# PiCarHat_Master_V2.net
KiCad netlist of a schematic drawn in Altium Designer
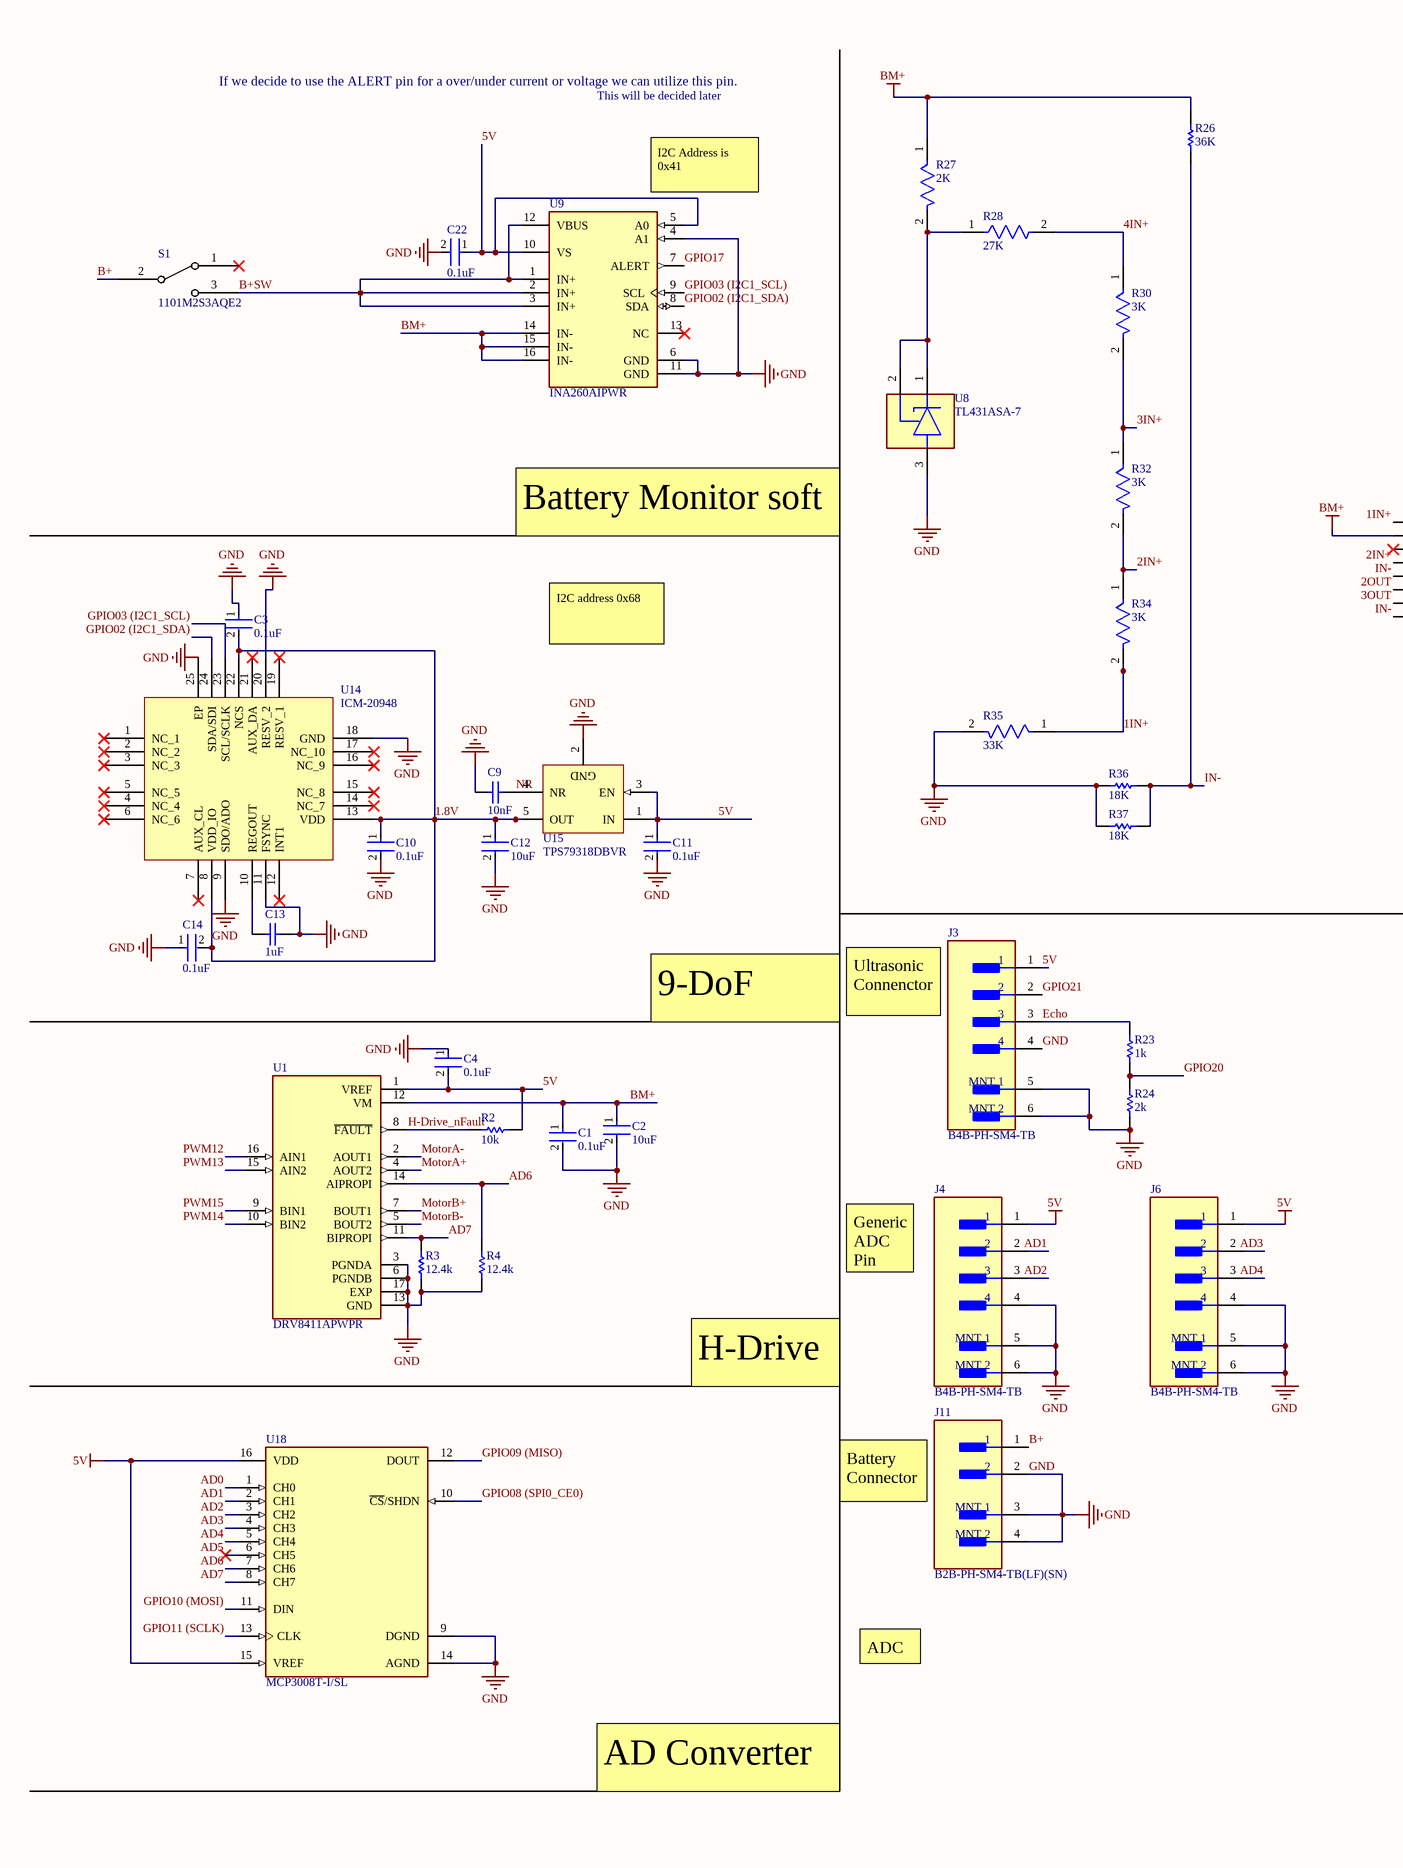
[diagram p0: PiCarHat_Master_V2.SchDoc, left]
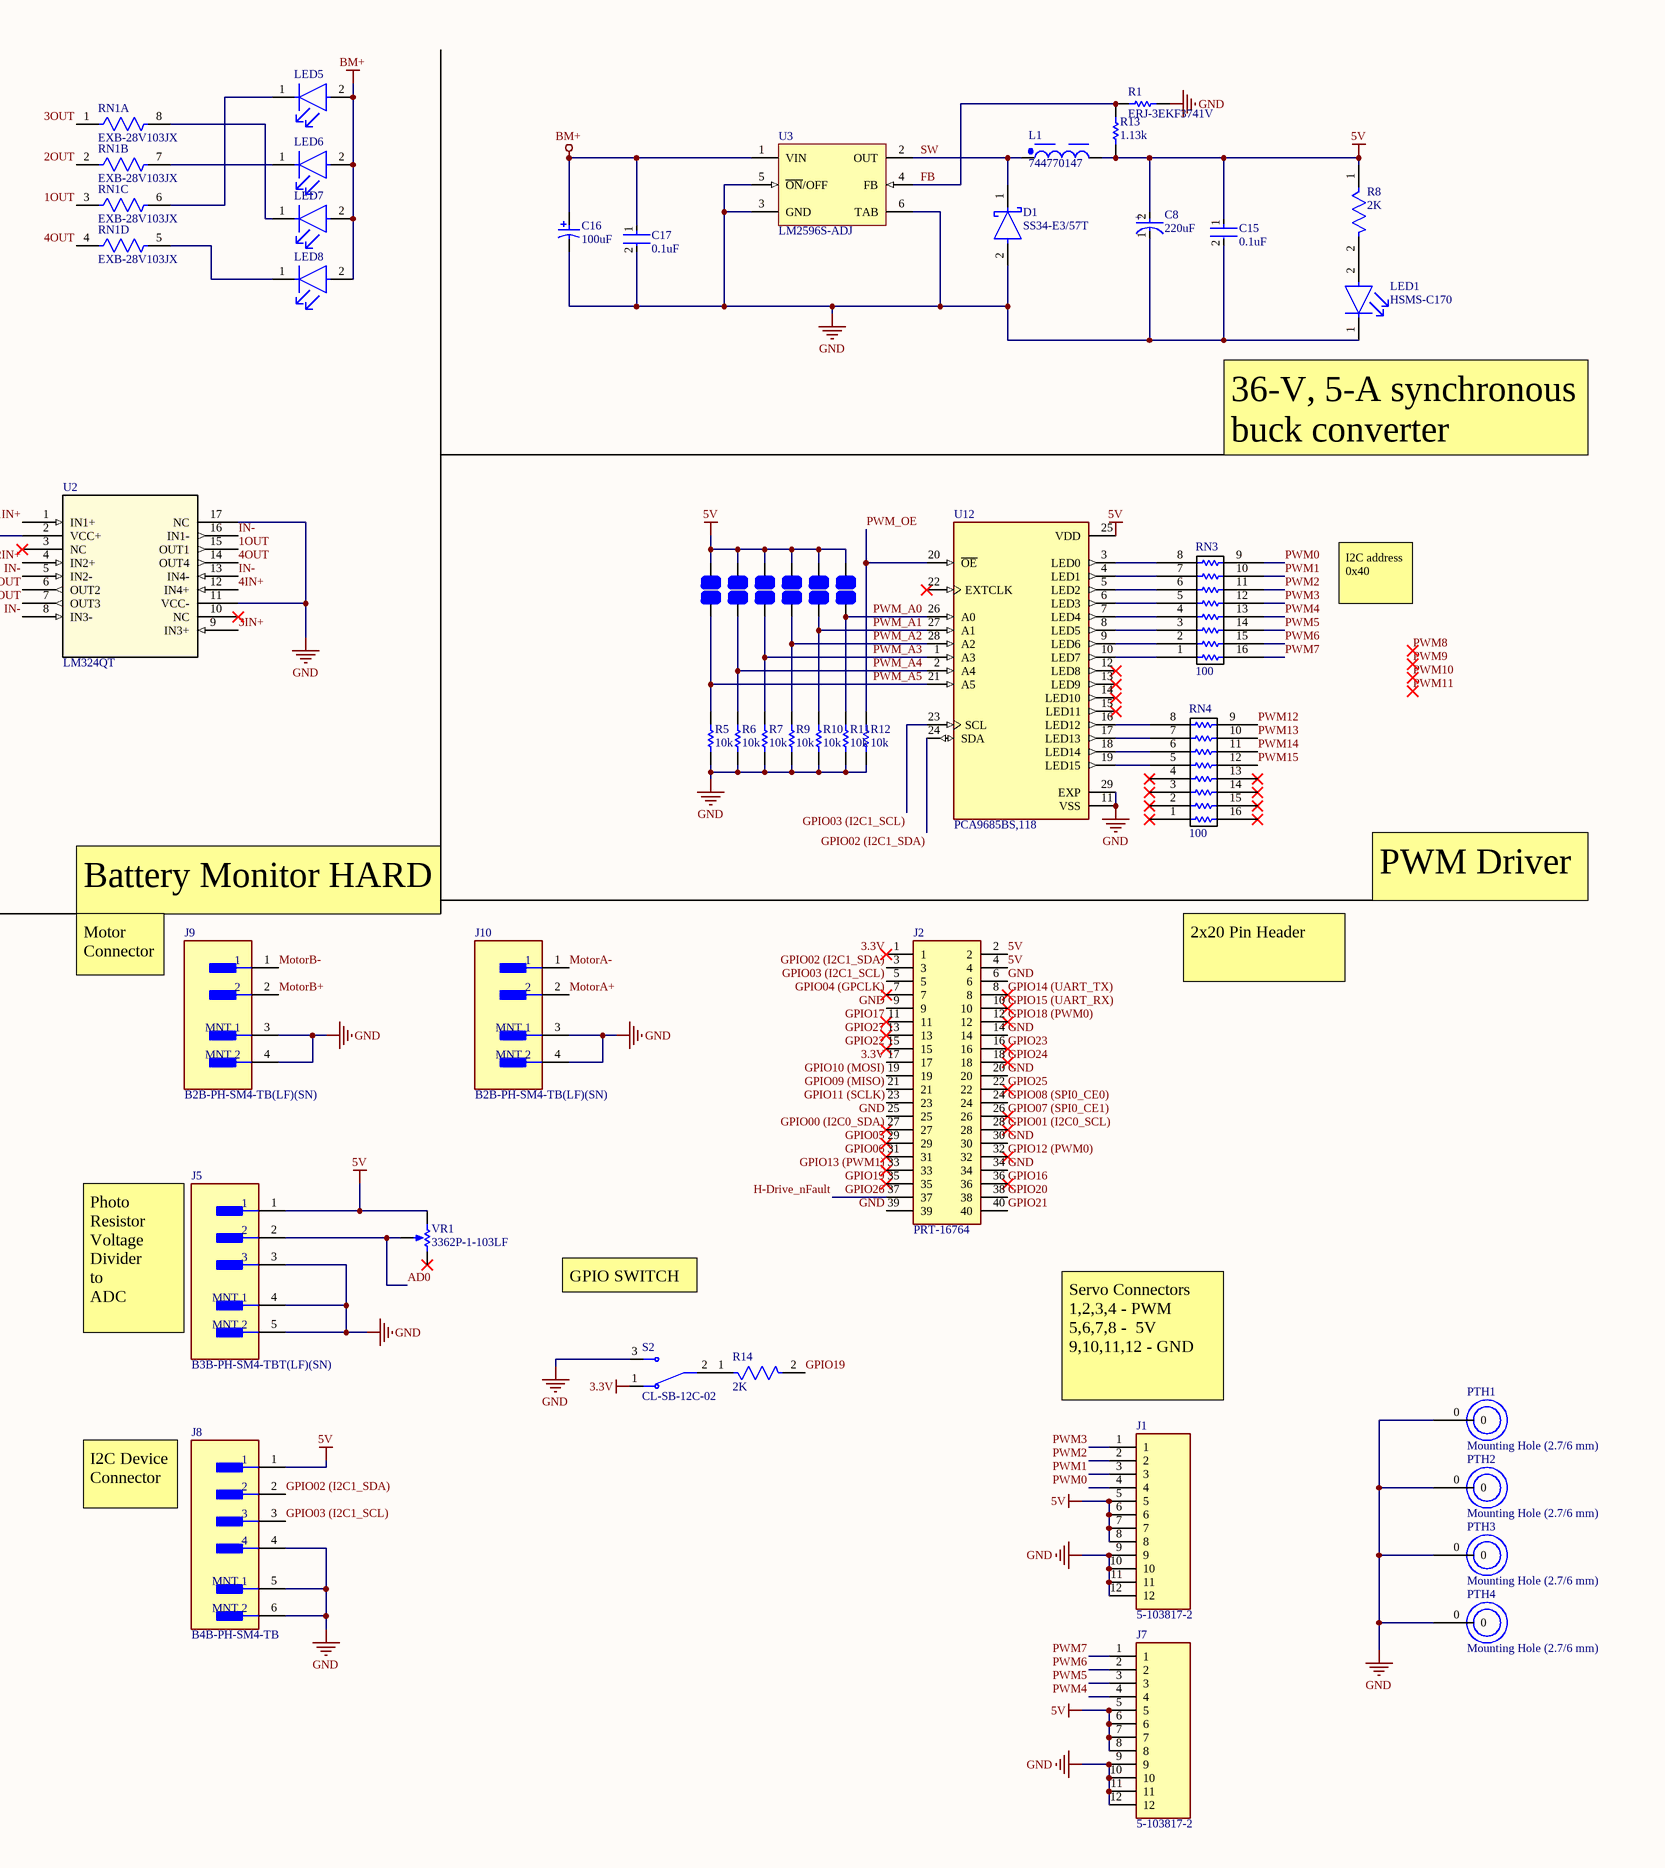
[diagram p1: PiCarHat_Master_V2.SchDoc, right]

(export (version "E")
  (design (tool "Eeschema 10.0.6"))
  (components
    (comp (ref "C1")
      (value "0.1uF")
      (footprint "FP-C1206C-EB-MFG")
      (description "C1206 0.10 μF X7R 10.00% 100 V")
      (fields (field (name "TOLERANCE") "0.1"))
      (libsource (lib "Altium Content Vault") (part "b4654b650e69147ec39a6b967a45e02"))
    )
    (comp (ref "C2")
      (value "10uF")
      (footprint "FP-GRM21B-0_15-IPC_C")
      (description "Chip Multilayer Ceramic Capacitors for General Purpose, 0805, 10uF, X5R, 15%, 10%, 25V")
      (fields (field (name "VOLTAGE") "25V") (field (name "TOLERANCE") "10%"))
      (libsource (lib "Altium Content Vault") (part "b4654b650e69147ec39a6b967a45e02"))
    )
    (comp (ref "C3")
      (value "0.1uF")
      (footprint "FP-C1206C-EB-MFG")
      (description "C1206 0.10 μF X7R 10.00% 100 V")
      (fields (field (name "TOLERANCE") "0.1"))
      (libsource (lib "Altium Content Vault") (part "b4654b650e69147ec39a6b967a45e02"))
    )
    (comp (ref "C4")
      (value "0.1uF")
      (footprint "FP-C1206C-EB-MFG")
      (description "C1206 0.10 μF X7R 10.00% 100 V")
      (fields (field (name "TOLERANCE") "0.1"))
      (libsource (lib "Altium Content Vault") (part "b4654b650e69147ec39a6b967a45e02"))
    )
    (comp (ref "C8")
      (value "220uF")
      (footprint "FP-FKG-MFG")
      (description "CAP ALUM 220UF 20% 50V SMD")
      (fields (field (name "TOLERANCE") "20%") (field (name "MANUFACTURER") "Panasonic"))
      (libsource (lib "Altium Content Vault") (part "203bc49f2ac43e59fd269a8c329ed05"))
    )
    (comp (ref "C9")
      (value "10nF")
      (footprint "CAPC2013X100X50NL20T25")
      (description "50V 10nF X7R ±10% 0805 Multilayer Ceramic Capacitors MLCC - SMD/SMT ROHS")
      (fields (field (name "PART NUMBER") "C0805F103K5RACTU") (field (name "MANUFACTURER") "Kemet"))
      (libsource (lib "Altium Content Vault") (part "CAP"))
    )
    (comp (ref "C10")
      (value "0.1uF")
      (footprint "FP-C1206C-EB-MFG")
      (description "C1206 0.10 μF X7R 10.00% 100 V")
      (fields (field (name "TOLERANCE") "0.1"))
      (libsource (lib "Altium Content Vault") (part "b4654b650e69147ec39a6b967a45e02"))
    )
    (comp (ref "C11")
      (value "0.1uF")
      (footprint "FP-C1206C-EB-MFG")
      (description "C1206 0.10 μF X7R 10.00% 100 V")
      (fields (field (name "TOLERANCE") "0.1"))
      (libsource (lib "Altium Content Vault") (part "b4654b650e69147ec39a6b967a45e02"))
    )
    (comp (ref "C12")
      (value "10uF")
      (footprint "FP-GRM21B-0_15-IPC_C")
      (description "Chip Multilayer Ceramic Capacitors for General Purpose, 0805, 10uF, X5R, 15%, 10%, 25V")
      (fields (field (name "VOLTAGE") "25V") (field (name "TOLERANCE") "10%"))
      (libsource (lib "Altium Content Vault") (part "b4654b650e69147ec39a6b967a45e02"))
    )
    (comp (ref "C13")
      (value "1uF")
      (footprint "CAPC2013X140X50LL20T25")
      (description "25V 1uF X7R ±10% 0805 Multilayer Ceramic Capacitors MLCC - SMD/SMT ROHS")
      (fields (field (name "PART NUMBER") "C0805C105K3RACTU") (field (name "MANUFACTURER") "Kemet"))
      (libsource (lib "Altium Content Vault") (part "CAP"))
    )
    (comp (ref "C14")
      (value "0.1uF")
      (footprint "FP-C1206C-EB-MFG")
      (description "C1206 0.10 μF X7R 10.00% 100 V")
      (fields (field (name "TOLERANCE") "0.1"))
      (libsource (lib "Altium Content Vault") (part "b4654b650e69147ec39a6b967a45e02"))
    )
    (comp (ref "C15")
      (value "0.1uF")
      (footprint "FP-C1206C-EB-MFG")
      (description "C1206 0.10 μF X7R 10.00% 100 V")
      (fields (field (name "TOLERANCE") "0.1"))
      (libsource (lib "Altium Content Vault") (part "b4654b650e69147ec39a6b967a45e02"))
    )
    (comp (ref "C16")
      (value "100uF")
      (footprint "PNSC-FK-V-D8_V")
      (fields (field (name "MANUFACTURER") "Panasonic") (field (name "PART NUMBER") "EEE-FK1E101XP"))
      (libsource (lib "Altium Content Vault") (part "CAP-P-2"))
    )
    (comp (ref "C17")
      (value "0.1uF")
      (footprint "FP-C1206C-EB-MFG")
      (description "C1206 0.10 μF X7R 10.00% 100 V")
      (fields (field (name "TOLERANCE") "0.1"))
      (libsource (lib "Altium Content Vault") (part "b4654b650e69147ec39a6b967a45e02"))
    )
    (comp (ref "C22")
      (value "0.1uF")
      (footprint "FP-C1206C-EB-MFG")
      (description "C1206 0.10 μF X7R 10.00% 100 V")
      (fields (field (name "TOLERANCE") "0.1"))
      (libsource (lib "Altium Content Vault") (part "b4654b650e69147ec39a6b967a45e02"))
    )
    (comp (ref "D1")
      (value "SS34-E3/57T")
      (footprint "FP-95402-MFG")
      (description "DIODE SCHOTTKY 40V 3A DO214AB")
      (fields
        (field (name "MANUFACTURER") "Vishay")
        (field (name "OCTOPART") "https://octopart.com/ss34-e3%2F57t-vishay-39552907")
      )
      (libsource (lib "Altium Content Vault") (part "1d6ec82d83fb6aee721767c19dac4b9"))
    )
    (comp (ref "J1")
      (value "5-103817-2")
      (footprint "TE_5-103817-2")
      (description "12 MODII HDR 3RST UNSHRD .100")
      (fields (field (name "MF") "TE Connectivity") (field (name "PART NUMBER") "TSW-104-07-L-T"))
      (libsource (lib "Ethan Morton Personal") (part "5-103817-2"))
    )
    (comp (ref "J2")
      (value "PRT-16764")
      (footprint "PiCarHat:RHDR40W64P254_2X20_5130X500X1375P")
      (description "Connector")
      (fields (field (name "MOUSER PART NUMBER") "474-PRT-16764"))
      (libsource (lib "PiCarHat") (part "PRT-16764"))
    )
    (comp (ref "J3")
      (value "B4B-PH-SM4-TB")
      (footprint "FP-B4B-PH-SM4-TB-MFG")
      (description "2.0mm pitch/Disconnectable Insulation displacement and Crimp style connectors")
      (libsource (lib "Ethan Morton Personal") (part "f4320a1371cd6270e33bce1916c33c0"))
    )
    (comp (ref "J4")
      (value "B4B-PH-SM4-TB")
      (footprint "FP-B4B-PH-SM4-TB-MFG")
      (description "2.0mm pitch/Disconnectable Insulation displacement and Crimp style connectors")
      (libsource (lib "Ethan Morton Personal") (part "f4320a1371cd6270e33bce1916c33c0"))
    )
    (comp (ref "J5")
      (value "B3B-PH-SM4-TBT(LF)(SN)")
      (footprint "FP-B3B-PH-SM4-TBT_LF_SN-MFG")
      (fields (field (name "PART NUMBER") "B3B-PH-SM4-TB"))
      (libsource (lib "Ethan Morton Personal") (part "38689d6f3df0f9b234c6ddcef280d85"))
    )
    (comp (ref "J6")
      (value "B4B-PH-SM4-TB")
      (footprint "FP-B4B-PH-SM4-TB-MFG")
      (description "2.0mm pitch/Disconnectable Insulation displacement and Crimp style connectors")
      (libsource (lib "Ethan Morton Personal") (part "f4320a1371cd6270e33bce1916c33c0"))
    )
    (comp (ref "J7")
      (value "5-103817-2")
      (footprint "TE_5-103817-2")
      (description "12 MODII HDR 3RST UNSHRD .100")
      (fields (field (name "PART NUMBER") "TSW-104-07-L-T") (field (name "MF") "TE Connectivity"))
      (libsource (lib "Ethan Morton Personal") (part "5-103817-2"))
    )
    (comp (ref "J8")
      (value "B4B-PH-SM4-TB")
      (footprint "FP-B4B-PH-SM4-TB-MFG")
      (description "2.0mm pitch/Disconnectable Insulation displacement and Crimp style connectors")
      (libsource (lib "Ethan Morton Personal") (part "f4320a1371cd6270e33bce1916c33c0"))
    )
    (comp (ref "J9")
      (value "B2B-PH-SM4-TB(LF)(SN)")
      (footprint "FP-B2B-PH-SM4-TB_LF_SN-MFG")
      (description "Connector Header, PH Series, 2 Position, 2.00mm, 100V, Surface Mount, Solder, Natural")
      (fields (field (name "PART NUMBER") "B2B-PH-SM4-TB"))
      (libsource (lib "Ethan Morton Personal") (part "56ec3178a87b3978bdc1b3682cd516a"))
    )
    (comp (ref "J10")
      (value "B2B-PH-SM4-TB(LF)(SN)")
      (footprint "FP-B2B-PH-SM4-TB_LF_SN-MFG")
      (description "Connector Header, PH Series, 2 Position, 2.00mm, 100V, Surface Mount, Solder, Natural")
      (fields (field (name "PART NUMBER") "B2B-PH-SM4-TB"))
      (libsource (lib "Ethan Morton Personal") (part "56ec3178a87b3978bdc1b3682cd516a"))
    )
    (comp (ref "J11")
      (value "B2B-PH-SM4-TB(LF)(SN)")
      (footprint "FP-B2B-PH-SM4-TB_LF_SN-MFG")
      (description "Connector Header, PH Series, 2 Position, 2.00mm, 100V, Surface Mount, Solder, Natural")
      (fields (field (name "PART NUMBER") "B2B-PH-SM4-TB"))
      (libsource (lib "Ethan Morton Personal") (part "56ec3178a87b3978bdc1b3682cd516a"))
    )
    (comp (ref "L1")
      (value "744770147")
      (footprint "WE-PD_1280")
      (fields (field (name "TOLERANCE") "20%"))
      (libsource (lib "Altium Content Vault") (part "Inductor - 2"))
    )
    (comp (ref "LED1")
      (value "HSMS-C170")
      (footprint "HSMS-C170-Footprint-1")
      (description "Single Color LED, High Efficiency Red, Untinted Diffused, 1.4mm")
      (libsource (lib "Ethan Morton Personal") (part "Component_1"))
    )
    (comp (ref "LED5")
      (value "HSMS-C170")
      (footprint "HSMS-C170-Footprint-1")
      (description "Single Color LED, High Efficiency Red, Untinted Diffused, 1.4mm")
      (libsource (lib "Ethan Morton Personal") (part "Component_1"))
    )
    (comp (ref "LED6")
      (value "HSMS-C170")
      (footprint "HSMS-C170-Footprint-1")
      (description "Single Color LED, High Efficiency Red, Untinted Diffused, 1.4mm")
      (libsource (lib "Ethan Morton Personal") (part "Component_1"))
    )
    (comp (ref "LED7")
      (value "HSMS-C170")
      (footprint "HSMS-C170-Footprint-1")
      (description "Single Color LED, High Efficiency Red, Untinted Diffused, 1.4mm")
      (libsource (lib "Ethan Morton Personal") (part "Component_1"))
    )
    (comp (ref "LED8")
      (value "HSMS-C170")
      (footprint "HSMS-C170-Footprint-1")
      (description "Single Color LED, High Efficiency Red, Untinted Diffused, 1.4mm")
      (libsource (lib "Ethan Morton Personal") (part "Component_1"))
    )
    (comp (ref "PD1")
      (value "0805 Solder pads, 51mil x 28mil, Gap 47 mil")
      (footprint "0805 Solder Pads")
      (libsource (lib "PiCarHat") (part "0805 Pads"))
    )
    (comp (ref "PD2")
      (value "0805 Solder pads, 51mil x 28mil, Gap 47 mil")
      (footprint "0805 Solder Pads")
      (libsource (lib "PiCarHat") (part "0805 Pads"))
    )
    (comp (ref "PD3")
      (value "0805 Solder pads, 51mil x 28mil, Gap 47 mil")
      (footprint "0805 Solder Pads")
      (libsource (lib "PiCarHat") (part "0805 Pads"))
    )
    (comp (ref "PD4")
      (value "0805 Solder pads, 51mil x 28mil, Gap 47 mil")
      (footprint "0805 Solder Pads")
      (libsource (lib "PiCarHat") (part "0805 Pads"))
    )
    (comp (ref "PD5")
      (value "0805 Solder pads, 51mil x 28mil, Gap 47 mil")
      (footprint "0805 Solder Pads")
      (libsource (lib "PiCarHat") (part "0805 Pads"))
    )
    (comp (ref "PD6")
      (value "0805 Solder pads, 51mil x 28mil, Gap 47 mil")
      (footprint "0805 Solder Pads")
      (libsource (lib "PiCarHat") (part "0805 Pads"))
    )
    (comp (ref "PTH1")
      (value "Mounting Hole (2.7/6 mm)")
      (footprint "New footprint 1")
      (description "Mounting Hole with inner diameter of 2.7mm and outer diameter of 6mm (Made for Rasberry Pi 4b")
      (libsource (lib "Ethan Morton Personal") (part "Mounting Hole (2.7/6 mm)"))
    )
    (comp (ref "PTH2")
      (value "Mounting Hole (2.7/6 mm)")
      (footprint "New footprint 1")
      (description "Mounting Hole with inner diameter of 2.7mm and outer diameter of 6mm (Made for Rasberry Pi 4b")
      (libsource (lib "Ethan Morton Personal") (part "Mounting Hole (2.7/6 mm)"))
    )
    (comp (ref "PTH3")
      (value "Mounting Hole (2.7/6 mm)")
      (footprint "New footprint 1")
      (description "Mounting Hole with inner diameter of 2.7mm and outer diameter of 6mm (Made for Rasberry Pi 4b")
      (libsource (lib "Ethan Morton Personal") (part "Mounting Hole (2.7/6 mm)"))
    )
    (comp (ref "PTH4")
      (value "Mounting Hole (2.7/6 mm)")
      (footprint "New footprint 1")
      (description "Mounting Hole with inner diameter of 2.7mm and outer diameter of 6mm (Made for Rasberry Pi 4b")
      (libsource (lib "Ethan Morton Personal") (part "Mounting Hole (2.7/6 mm)"))
    )
    (comp (ref "R1")
      (value "ERJ-3EKF3741V")
      (footprint "RESC1608X55X30LL15T15")
      (fields (field (name "MANUFACTURER") "Panasonic"))
      (libsource (lib "Altium Content Vault") (part "RES"))
    )
    (comp (ref "R2")
      (value "10k")
      (footprint "RESC1608X55X25LL10T15")
      (fields
        (field (name "MANUFACTURER") "Yageo")
        (field (name "TOLERANCE") "5%")
        (field (name "PART NUMBER") "RC0603JR-0710KL")
      )
      (libsource (lib "Altium Content Vault") (part "RES-2"))
    )
    (comp (ref "R3")
      (value "12.4k")
      (footprint "RESC2013X60X35NL10T20")
      (fields (field (name "PART NUMBER") "RC0805FR-0712K4L") (field (name "MANUFACTURER") "Yageo"))
      (libsource (lib "Altium Content Vault") (part "RES"))
    )
    (comp (ref "R4")
      (value "12.4k")
      (footprint "RESC2013X60X35NL10T20")
      (fields (field (name "PART NUMBER") "RC0805FR-0712K4L") (field (name "MANUFACTURER") "Yageo"))
      (libsource (lib "Altium Content Vault") (part "RES"))
    )
    (comp (ref "R5")
      (value "10k")
      (footprint "RESC1608X55X25ML10T15")
      (fields
        (field (name "MANUFACTURER") "Yageo")
        (field (name "TOLERANCE") "5%")
        (field (name "PART NUMBER") "RC0603JR-0710KL")
      )
      (libsource (lib "Altium Content Vault") (part "RES-2"))
    )
    (comp (ref "R6")
      (value "10k")
      (footprint "RESC1608X55X25ML10T15")
      (fields
        (field (name "MANUFACTURER") "Yageo")
        (field (name "TOLERANCE") "5%")
        (field (name "PART NUMBER") "RC0603JR-0710KL")
      )
      (libsource (lib "Altium Content Vault") (part "RES-2"))
    )
    (comp (ref "R7")
      (value "10k")
      (footprint "RESC1608X55X25ML10T15")
      (fields
        (field (name "MANUFACTURER") "Yageo")
        (field (name "TOLERANCE") "5%")
        (field (name "PART NUMBER") "RC0603JR-0710KL")
      )
      (libsource (lib "Altium Content Vault") (part "RES-2"))
    )
    (comp (ref "R8")
      (value "2K")
      (footprint "FP-CRCW0805-e3-MFG")
      (description "RES Thick Film, 2kΩ, 1%, 0.125W, 100ppm/°C, 0805")
      (fields (field (name "TOLERANCE") "1%") (field (name "PART NUMBER") "CRCW08052K00FKEA"))
      (libsource (lib "Altium Content Vault") (part "1029c3af85768c4190bb7ad29bc67b5"))
    )
    (comp (ref "R9")
      (value "10k")
      (footprint "RESC1608X55X25ML10T15")
      (fields
        (field (name "MANUFACTURER") "Yageo")
        (field (name "TOLERANCE") "5%")
        (field (name "PART NUMBER") "RC0603JR-0710KL")
      )
      (libsource (lib "Altium Content Vault") (part "RES-2"))
    )
    (comp (ref "R10")
      (value "10k")
      (footprint "RESC1608X55X25ML10T15")
      (fields
        (field (name "MANUFACTURER") "Yageo")
        (field (name "TOLERANCE") "5%")
        (field (name "PART NUMBER") "RC0603JR-0710KL")
      )
      (libsource (lib "Altium Content Vault") (part "RES-2"))
    )
    (comp (ref "R11")
      (value "10k")
      (footprint "RESC1608X55X25ML10T15")
      (fields
        (field (name "MANUFACTURER") "Yageo")
        (field (name "TOLERANCE") "5%")
        (field (name "PART NUMBER") "RC0603JR-0710KL")
      )
      (libsource (lib "Altium Content Vault") (part "RES-2"))
    )
    (comp (ref "R12")
      (value "10k")
      (footprint "RESC1608X55X25ML10T15")
      (fields
        (field (name "MANUFACTURER") "Yageo")
        (field (name "TOLERANCE") "5%")
        (field (name "PART NUMBER") "RC0603JR-0710KL")
      )
      (libsource (lib "Altium Content Vault") (part "RES-2"))
    )
    (comp (ref "R13")
      (value "1.13k")
      (footprint "RESC1609X50X30NL10T20")
      (fields (field (name "PART NUMBER") "CRCW06031K13FKEA") (field (name "MANUFACTURER") "Vishay Dale"))
      (libsource (lib "Altium Content Vault") (part "RES"))
    )
    (comp (ref "R14")
      (value "2K")
      (footprint "FP-CRCW0805-e3-MFG")
      (description "RES Thick Film, 2kΩ, 1%, 0.125W, 100ppm/°C, 0805")
      (fields (field (name "TOLERANCE") "1%") (field (name "PART NUMBER") "CRCW08052K00FKEA"))
      (libsource (lib "Altium Content Vault") (part "1029c3af85768c4190bb7ad29bc67b5"))
    )
    (comp (ref "R23")
      (value "1k")
      (footprint "RESC1609X55X30LL10T20")
      (fields (field (name "PART NUMBER") "TNPW06031K00BETA") (field (name "MANUFACTURER") "Vishay Dale"))
      (libsource (lib "Altium Content Vault") (part "RES"))
    )
    (comp (ref "R24")
      (value "2k")
      (footprint "RESC1609X55X30LL10T20")
      (fields (field (name "PART NUMBER") "TNPW06032K00BEEA") (field (name "MANUFACTURER") "Vishay Dale"))
      (libsource (lib "Altium Content Vault") (part "RES"))
    )
    (comp (ref "R26")
      (value "36K")
      (footprint "RESC2113X50X35ML15T15")
      (description "Chip Resistor, 36 KOhm, +/- 1%, 0.125 W, -55 to 155 degC, 0805 (2012 Metric), RoHS, Tape and Reel")
      (fields
        (field (name "MANUFACTURER") "Vishay Semiconductor")
        (field (name "PART NUMBER") "CRCW080536K0FKEA")
      )
      (libsource (lib "Altium Content Vault") (part "RES-2"))
    )
    (comp (ref "R27")
      (value "2K")
      (footprint "FP-CRCW0805-e3-IPC_B")
      (description "RES Thick Film, 2kΩ, 1%, 0.125W, 100ppm/°C, 0805")
      (fields (field (name "TOLERANCE") "1%") (field (name "PART NUMBER") "CRCW08052K00FKEA"))
      (libsource (lib "Altium Content Vault") (part "1029c3af85768c4190bb7ad29bc67b5"))
    )
    (comp (ref "R28")
      (value "27K")
      (footprint "FP-CRCW0805-e3-MFG")
      (description "RES Thick Film, 27kΩ, 1%, 0.125W, 100ppm/°C, 0805")
      (fields (field (name "TOLERANCE") "1%") (field (name "PART NUMBER") "CRCW080527K0FKEA"))
      (libsource (lib "Altium Content Vault") (part "1029c3af85768c4190bb7ad29bc67b5"))
    )
    (comp (ref "R30")
      (value "3K")
      (footprint "FP-CRCW0805-e3-IPC_C")
      (description "RES Thick Film, 3kΩ, 1%, 0.125W, 100ppm/°C, 0805")
      (fields (field (name "TOLERANCE") "1%") (field (name "PART NUMBER") "CRCW08053K00FKEA"))
      (libsource (lib "Altium Content Vault") (part "1029c3af85768c4190bb7ad29bc67b5"))
    )
    (comp (ref "R32")
      (value "3K")
      (footprint "FP-CRCW0805-e3-IPC_C")
      (description "RES Thick Film, 3kΩ, 1%, 0.125W, 100ppm/°C, 0805")
      (fields (field (name "TOLERANCE") "1%") (field (name "PART NUMBER") "CRCW08053K00FKEA"))
      (libsource (lib "Altium Content Vault") (part "1029c3af85768c4190bb7ad29bc67b5"))
    )
    (comp (ref "R34")
      (value "3K")
      (footprint "FP-CRCW0805-e3-IPC_C")
      (description "RES Thick Film, 3kΩ, 1%, 0.125W, 100ppm/°C, 0805")
      (fields (field (name "TOLERANCE") "1%") (field (name "PART NUMBER") "CRCW08053K00FKEA"))
      (libsource (lib "Altium Content Vault") (part "1029c3af85768c4190bb7ad29bc67b5"))
    )
    (comp (ref "R35")
      (value "33K")
      (footprint "FP-CRCW0805-e3-IPC_B")
      (description "RES Thick Film, 33kΩ, 1%, 0.125W, 100ppm/°C, 0805")
      (fields (field (name "TOLERANCE") "1%") (field (name "PART NUMBER") "CRCW080533K0FKEA"))
      (libsource (lib "Altium Content Vault") (part "1029c3af85768c4190bb7ad29bc67b5"))
    )
    (comp (ref "R36")
      (value "18K")
      (footprint "RESC2013X50X30NL20T20")
      (fields (field (name "PART NUMBER") "CRCW080518K0FKEA") (field (name "MANUFACTURER") "Vishay Dale"))
      (libsource (lib "Altium Content Vault") (part "RES"))
    )
    (comp (ref "R37")
      (value "18K")
      (footprint "RESC2013X50X30NL20T20")
      (fields (field (name "PART NUMBER") "CRCW080518K0FKEA") (field (name "MANUFACTURER") "Vishay Dale"))
      (libsource (lib "Altium Content Vault") (part "RES"))
    )
    (comp (ref "RN1")
      (value "EXB-28V103JX")
      (footprint "FP-EXB28V-MFG")
      (description "RES ARRAY 4 RES 10K OHM 0804")
      (fields (field (name "TOLERANCE") "5%") (field (name "PART NUMBER") "EXB-28V103JX Panasonic"))
      (libsource (lib "Altium Content Vault") (part "46c0e806a6f3a765a2d55930d12d044"))
    )
    (comp (ref "RN3")
      (value "100")
      (footprint "YC248-JR-07100RL-Footprint-2")
      (fields (field (name "TOLERANCE") "5%") (field (name "PART NUMBER") "YC248-JR-07100RL"))
      (libsource (lib "Ethan Morton Personal") (part "YC248-JR-07100RL-Symbol-1"))
    )
    (comp (ref "RN4")
      (value "100")
      (footprint "YC248-JR-07100RL-Footprint-2")
      (fields (field (name "TOLERANCE") "5%") (field (name "PART NUMBER") "YC248-JR-07100RL"))
      (libsource (lib "Ethan Morton Personal") (part "YC248-JR-07100RL-Symbol-1"))
    )
    (comp (ref "S1")
      (value "1101M2S3AQE2")
      (footprint "1101M2S3AQE2-Footprint-1")
      (description "Switch, SPDT, Horizontal, 6A, 28VDC, Through Hole-right Angle")
      (libsource (lib "Ethan Morton Personal") (part "1101M2S3AQE2-Symbol-1"))
    )
    (comp (ref "S2")
      (value "CL-SB-12C-02")
      (footprint "CL-SB-12C-02-Footprint-1")
      (description "Slide Switch")
      (libsource (lib "Ethan Morton Personal") (part "CL-SB-12C-02-Symbol-1"))
    )
    (comp (ref "U1")
      (value "DRV8411APWPR")
      (footprint "IC_DRV8411APWPR")
      (description "1.65-V to 11-V, 4-A dual H-bridge motor driver with IPROPI current regulation")
      (fields (field (name "MF") "Texas Instruments"))
      (libsource (lib "Ethan Morton Personal") (part "DRV8411APWPR"))
    )
    (comp (ref "U2")
      (value "LM324QT")
      (footprint "LM324QT-Footprint-1")
      (description "Operational Amplifier, 4 Func, 9000uV Offset-Max, BIPolar, PQCC16")
      (libsource (lib "Ethan Morton Personal") (part "LM324QT-Symbol-1"))
    )
    (comp (ref "U3")
      (value "LM2596S-ADJ")
      (footprint "TS5B_L")
      (description "SIMPLE SWITCHER® Power Converter 150 KHz 3A Step-Down Voltage Regulator, 5-pin TO-263")
      (fields
        (field (name "MANUFACTURER") "National Semiconductor")
        (field (name "PART NUMBER") "4518-LM2596S-ADJTR-ND")
      )
      (libsource (lib "Altium Content Vault") (part "PM-REG-LM2575HVS-12"))
    )
    (comp (ref "U8")
      (value "TL431ASA-7")
      (footprint "FP-SOT23-MFG")
      (description "IC VREF SHUNT ADJ SOT23-3")
      (fields
        (field (name "OCTOPART") "https://octopart.com/tl431asa-7-diodes+inc.-18832779")
        (field (name "MANUFACTURER") "DIODES INC.")
      )
      (libsource (lib "Altium Content Vault") (part "bb7a1bf3cd7629b94a2ffd22ed0b9f9"))
    )
    (comp (ref "U9")
      (value "INA260AIPWR")
      (footprint "FP-PW0016A-MFG")
      (description "IC MONITOR PWR/CURR 16TSSOP")
      (fields
        (field (name "MANUFACTURER") "Texas Instruments")
        (field (name "OCTOPART") "https://octopart.com/ina260aipwr-texas+instruments-75199489")
      )
      (libsource (lib "Altium Content Vault") (part "fcceeca0fd405d0f0207f40a7ff7922"))
    )
    (comp (ref "U12")
      (value "PCA9685BS,118")
      (footprint "PiCarHat:QFN65P600X600X100-29N")
      (description "LED Driver IC 16 Output Linear PWM Dimming 25mA 28-HVQFN (6x6)")
      (fields (field (name "MF") "NXP USA"))
      (libsource (lib "Schlib1") (part "PCA9685BS,118"))
    )
    (comp (ref "U14")
      (value "ICM-20948")
      (footprint "TDK-QFN-24_L")
      (description "Accelerometer and Gyroscope Compass 9-Axis Digital 24-Pin QFN T/R")
      (libsource (lib "Ethan Morton Personal") (part "ICM-20948-Symbol-1"))
    )
    (comp (ref "U15")
      (value "TPS79318DBVR")
      (footprint "DBV0005A_M")
      (fields (field (name "MANUFACTURER") "Texas Instruments"))
      (libsource (lib "Altium Content Vault") (part "TI-TPS79NXX-YYSOT5"))
    )
    (comp (ref "U18")
      (value "MCP3008T-I/SL")
      (footprint "FP-C04-108-MFG")
      (description "IC ADC 10BIT SAR 16SOIC")
      (libsource (lib "Altium Content Vault") (part "049cb4bd9558e05d9b89494b6be139f"))
    )
    (comp (ref "VR1")
      (value "3362P-1-103LF")
      (footprint "BOUR-3362P")
      (description "Square Trimpot(R) Trimming Potentiometer, 10 KOhm, 300 V, -55 to 125 degC, 3-Pin THD, RoHS, Tube")
      (fields (field (name "TOLERANCE") "1%"))
      (libsource (lib "Altium Content Vault") (part "RES-POT-3"))
    )
  )
  (nets
    (net (code "1") (name "/1.8V") (class "Default")
      (node (ref "C10") (pin "1") (pinfunction "1_1") (pintype "passive"))
      (node (ref "C12") (pin "1") (pinfunction "1_1") (pintype "passive"))
      (node (ref "C14") (pin "2") (pinfunction "2_2") (pintype "passive"))
      (node (ref "C3") (pin "2") (pinfunction "2_2") (pintype "passive"))
      (node (ref "U14") (pin "13") (pinfunction "VDD_13") (pintype "passive"))
      (node (ref "U14") (pin "22") (pinfunction "NCS_22") (pintype "passive"))
      (node (ref "U14") (pin "8") (pinfunction "VDD_IO_8") (pintype "passive"))
      (node (ref "U15") (pin "5") (pinfunction "OUT_5") (pintype "power_in"))
    )
    (net (code "2") (name "/1IN+") (class "Default")
      (node (ref "R34") (pin "2") (pinfunction "2_2") (pintype "passive"))
      (node (ref "R35") (pin "1") (pinfunction "1_1") (pintype "passive"))
      (node (ref "U2") (pin "1") (pinfunction "IN1+_1") (pintype "input"))
    )
    (net (code "3") (name "/1OUT") (class "Default")
      (node (ref "RN1") (pin "3") (pinfunction "3_3") (pintype "passive"))
      (node (ref "U2") (pin "15") (pinfunction "OUT1_15") (pintype "output"))
    )
    (net (code "4") (name "/2IN+") (class "Default")
      (node (ref "R32") (pin "2") (pinfunction "2_2") (pintype "passive"))
      (node (ref "R34") (pin "1") (pinfunction "1_1") (pintype "passive"))
      (node (ref "U2") (pin "4") (pinfunction "IN2+_4") (pintype "input"))
    )
    (net (code "5") (name "/2OUT") (class "Default")
      (node (ref "RN1") (pin "2") (pinfunction "2_2") (pintype "passive"))
      (node (ref "U2") (pin "6") (pinfunction "OUT2_6") (pintype "output"))
    )
    (net (code "6") (name "/3IN+") (class "Default")
      (node (ref "R30") (pin "2") (pinfunction "2_2") (pintype "passive"))
      (node (ref "R32") (pin "1") (pinfunction "1_1") (pintype "passive"))
      (node (ref "U2") (pin "9") (pinfunction "IN3+_9") (pintype "input"))
    )
    (net (code "7") (name "/3OUT") (class "Default")
      (node (ref "RN1") (pin "1") (pinfunction "1_1") (pintype "passive"))
      (node (ref "U2") (pin "7") (pinfunction "OUT3_7") (pintype "output"))
    )
    (net (code "8") (name "/4IN+") (class "Default")
      (node (ref "R28") (pin "2") (pinfunction "2_2") (pintype "passive"))
      (node (ref "R30") (pin "1") (pinfunction "1_1") (pintype "passive"))
      (node (ref "U2") (pin "12") (pinfunction "IN4+_12") (pintype "input"))
    )
    (net (code "9") (name "/4OUT") (class "Default")
      (node (ref "RN1") (pin "4") (pinfunction "4_4") (pintype "passive"))
      (node (ref "U2") (pin "14") (pinfunction "OUT4_14") (pintype "output"))
    )
    (net (code "10") (name "/AD0") (class "Default")
      (node (ref "J5") (pin "2") (pinfunction "2_2") (pintype "passive"))
      (node (ref "U18") (pin "1") (pinfunction "CH0_1") (pintype "input"))
      (node (ref "VR1") (pin "2") (pinfunction "S_2") (pintype "passive"))
    )
    (net (code "11") (name "/AD1") (class "Default")
      (node (ref "J4") (pin "2") (pinfunction "2_2") (pintype "passive"))
      (node (ref "U18") (pin "2") (pinfunction "CH1_2") (pintype "input"))
    )
    (net (code "12") (name "/AD2") (class "Default")
      (node (ref "J4") (pin "3") (pinfunction "3_3") (pintype "passive"))
      (node (ref "U18") (pin "3") (pinfunction "CH2_3") (pintype "input"))
    )
    (net (code "13") (name "/AD3") (class "Default")
      (node (ref "J6") (pin "2") (pinfunction "2_2") (pintype "passive"))
      (node (ref "U18") (pin "4") (pinfunction "CH3_4") (pintype "input"))
    )
    (net (code "14") (name "/AD4") (class "Default")
      (node (ref "J6") (pin "3") (pinfunction "3_3") (pintype "passive"))
      (node (ref "U18") (pin "5") (pinfunction "CH4_5") (pintype "input"))
    )
    (net (code "15") (name "/AD5") (class "Default")
      (node (ref "U18") (pin "6") (pinfunction "CH5_6") (pintype "input+no_connect"))
    )
    (net (code "16") (name "/AD6") (class "Default")
      (node (ref "R4") (pin "2") (pinfunction "2_2") (pintype "passive"))
      (node (ref "U1") (pin "14") (pinfunction "AIPROPI_14") (pintype "output"))
      (node (ref "U18") (pin "7") (pinfunction "CH6_7") (pintype "input"))
    )
    (net (code "17") (name "/AD7") (class "Default")
      (node (ref "R3") (pin "2") (pinfunction "2_2") (pintype "passive"))
      (node (ref "U1") (pin "11") (pinfunction "BIPROPI_11") (pintype "output"))
      (node (ref "U18") (pin "8") (pinfunction "CH7_8") (pintype "input"))
    )
    (net (code "18") (name "/B+") (class "Default")
      (node (ref "J11") (pin "1") (pinfunction "1_1") (pintype "passive"))
      (node (ref "S1") (pin "2") (pinfunction "2_2") (pintype "passive"))
    )
    (net (code "19") (name "/B+SW") (class "Default")
      (node (ref "S1") (pin "3") (pinfunction "3_3") (pintype "passive"))
      (node (ref "U9") (pin "1") (pinfunction "IN+_1") (pintype "passive"))
      (node (ref "U9") (pin "12") (pinfunction "VBUS_12") (pintype "passive"))
      (node (ref "U9") (pin "2") (pinfunction "IN+_2") (pintype "passive"))
      (node (ref "U9") (pin "3") (pinfunction "IN+_3") (pintype "passive"))
    )
    (net (code "20") (name "/Echo") (class "Default")
      (node (ref "J3") (pin "3") (pinfunction "3_3") (pintype "passive"))
      (node (ref "R23") (pin "1") (pinfunction "1_1") (pintype "passive"))
    )
    (net (code "21") (name "/FB") (class "Default")
      (node (ref "R1") (pin "1") (pinfunction "1_1") (pintype "passive"))
      (node (ref "R13") (pin "2") (pinfunction "2_2") (pintype "passive"))
      (node (ref "U3") (pin "4") (pinfunction "FB_4") (pintype "input"))
    )
    (net (code "22") (name "/GPIO00 (I2C0_SDA)") (class "Default")
      (node (ref "J2") (pin "27") (pinfunction "27_27") (pintype "passive+no_connect"))
    )
    (net (code "23") (name "/GPIO01 (I2C0_SCL)") (class "Default")
      (node (ref "J2") (pin "28") (pinfunction "28_28") (pintype "passive+no_connect"))
    )
    (net (code "24") (name "/GPIO02 (I2C1_SDA)") (class "Default")
      (node (ref "J2") (pin "3") (pinfunction "3_3") (pintype "passive"))
      (node (ref "J8") (pin "2") (pinfunction "2_2") (pintype "passive"))
      (node (ref "U12") (pin "24") (pinfunction "SDA_24") (pintype "bidirectional"))
      (node (ref "U14") (pin "24") (pinfunction "SDA/SDI_24") (pintype "passive"))
      (node (ref "U9") (pin "8") (pinfunction "SDA_8") (pintype "bidirectional"))
    )
    (net (code "25") (name "/GPIO03 (I2C1_SCL)") (class "Default")
      (node (ref "J2") (pin "5") (pinfunction "5_5") (pintype "passive"))
      (node (ref "J8") (pin "3") (pinfunction "3_3") (pintype "passive"))
      (node (ref "U12") (pin "23") (pinfunction "SCL_23") (pintype "input"))
      (node (ref "U14") (pin "23") (pinfunction "SCL/SCLK_23") (pintype "passive"))
      (node (ref "U9") (pin "9") (pinfunction "SCL_9") (pintype "input"))
    )
    (net (code "26") (name "/GPIO04 (GPCLK)") (class "Default")
      (node (ref "J2") (pin "7") (pinfunction "7_7") (pintype "passive+no_connect"))
    )
    (net (code "27") (name "/GPIO05") (class "Default")
      (node (ref "J2") (pin "29") (pinfunction "29_29") (pintype "passive+no_connect"))
    )
    (net (code "28") (name "/GPIO06") (class "Default")
      (node (ref "J2") (pin "31") (pinfunction "31_31") (pintype "passive+no_connect"))
    )
    (net (code "29") (name "/GPIO07 (SPI0_CE1)") (class "Default")
      (node (ref "J2") (pin "26") (pinfunction "26_26") (pintype "passive+no_connect"))
    )
    (net (code "30") (name "/GPIO08 (SPI0_CE0)") (class "Default")
      (node (ref "J2") (pin "24") (pinfunction "24_24") (pintype "passive"))
      (node (ref "U18") (pin "10") (pinfunction "~{CS}/SHDN_10") (pintype "input"))
    )
    (net (code "31") (name "/GPIO09 (MISO)") (class "Default")
      (node (ref "J2") (pin "21") (pinfunction "21_21") (pintype "passive"))
      (node (ref "U18") (pin "12") (pinfunction "DOUT_12") (pintype "tri_state"))
    )
    (net (code "32") (name "/GPIO10 (MOSI)") (class "Default")
      (node (ref "J2") (pin "19") (pinfunction "19_19") (pintype "passive"))
      (node (ref "U18") (pin "11") (pinfunction "DIN_11") (pintype "input"))
    )
    (net (code "33") (name "/GPIO11 (SCLK)") (class "Default")
      (node (ref "J2") (pin "23") (pinfunction "23_23") (pintype "passive"))
      (node (ref "U18") (pin "13") (pinfunction "CLK_13") (pintype "input"))
    )
    (net (code "34") (name "/GPIO12 (PWM0)") (class "Default")
      (node (ref "J2") (pin "32") (pinfunction "32_32") (pintype "passive+no_connect"))
    )
    (net (code "35") (name "/GPIO13 (PWM1)") (class "Default")
      (node (ref "J2") (pin "33") (pinfunction "33_33") (pintype "passive+no_connect"))
    )
    (net (code "36") (name "/GPIO14 (UART_TX)") (class "Default")
      (node (ref "J2") (pin "8") (pinfunction "8_8") (pintype "passive+no_connect"))
    )
    (net (code "37") (name "/GPIO15 (UART_RX)") (class "Default")
      (node (ref "J2") (pin "10") (pinfunction "10_10") (pintype "passive+no_connect"))
    )
    (net (code "38") (name "/GPIO16") (class "Default")
      (node (ref "J2") (pin "36") (pinfunction "36_36") (pintype "passive+no_connect"))
    )
    (net (code "39") (name "/GPIO17") (class "Default")
      (node (ref "J2") (pin "11") (pinfunction "11_11") (pintype "passive"))
      (node (ref "U9") (pin "7") (pinfunction "ALERT_7") (pintype "output"))
    )
    (net (code "40") (name "/GPIO18 (PWM0)") (class "Default")
      (node (ref "J2") (pin "12") (pinfunction "12_12") (pintype "passive+no_connect"))
    )
    (net (code "41") (name "/GPIO19") (class "Default")
      (node (ref "J2") (pin "35") (pinfunction "35_35") (pintype "passive"))
      (node (ref "R14") (pin "2") (pinfunction "2_2") (pintype "passive"))
    )
    (net (code "42") (name "/GPIO20") (class "Default")
      (node (ref "J2") (pin "38") (pinfunction "38_38") (pintype "passive"))
      (node (ref "R23") (pin "2") (pinfunction "2_2") (pintype "passive"))
      (node (ref "R24") (pin "1") (pinfunction "1_1") (pintype "passive"))
    )
    (net (code "43") (name "/GPIO21") (class "Default")
      (node (ref "J2") (pin "40") (pinfunction "40_40") (pintype "passive"))
      (node (ref "J3") (pin "2") (pinfunction "2_2") (pintype "passive"))
    )
    (net (code "44") (name "/GPIO22") (class "Default")
      (node (ref "J2") (pin "15") (pinfunction "15_15") (pintype "passive+no_connect"))
    )
    (net (code "45") (name "/GPIO23") (class "Default")
      (node (ref "J2") (pin "16") (pinfunction "16_16") (pintype "passive+no_connect"))
    )
    (net (code "46") (name "/GPIO24") (class "Default")
      (node (ref "J2") (pin "18") (pinfunction "18_18") (pintype "passive+no_connect"))
    )
    (net (code "47") (name "/GPIO25") (class "Default")
      (node (ref "J2") (pin "22") (pinfunction "22_22") (pintype "passive+no_connect"))
    )
    (net (code "48") (name "/GPIO26") (class "Default")
      (node (ref "J2") (pin "37") (pinfunction "37_37") (pintype "passive"))
      (node (ref "R2") (pin "2") (pinfunction "2_2") (pintype "passive"))
      (node (ref "U1") (pin "8") (pinfunction "~{FAULT}_8") (pintype "output"))
    )
    (net (code "49") (name "/GPIO27") (class "Default")
      (node (ref "J2") (pin "13") (pinfunction "13_13") (pintype "passive+no_connect"))
    )
    (net (code "50") (name "/IN-") (class "Default")
      (node (ref "R26") (pin "1") (pinfunction "1_1") (pintype "passive"))
      (node (ref "R36") (pin "2") (pinfunction "2_2") (pintype "passive"))
      (node (ref "R37") (pin "2") (pinfunction "2_2") (pintype "passive"))
      (node (ref "U2") (pin "13") (pinfunction "IN4-_13") (pintype "input"))
      (node (ref "U2") (pin "16") (pinfunction "IN1-_16") (pintype "output"))
      (node (ref "U2") (pin "5") (pinfunction "IN2-_5") (pintype "input"))
      (node (ref "U2") (pin "8") (pinfunction "IN3-_8") (pintype "input"))
    )
    (net (code "51") (name "/MotorA+") (class "Default")
      (node (ref "J10") (pin "2") (pinfunction "2_2") (pintype "passive"))
      (node (ref "U1") (pin "4") (pinfunction "AOUT2_4") (pintype "output"))
    )
    (net (code "52") (name "/MotorA-") (class "Default")
      (node (ref "J10") (pin "1") (pinfunction "1_1") (pintype "passive"))
      (node (ref "U1") (pin "2") (pinfunction "AOUT1_2") (pintype "output"))
    )
    (net (code "53") (name "/MotorB+") (class "Default")
      (node (ref "J9") (pin "2") (pinfunction "2_2") (pintype "passive"))
      (node (ref "U1") (pin "7") (pinfunction "BOUT1_7") (pintype "output"))
    )
    (net (code "54") (name "/MotorB-") (class "Default")
      (node (ref "J9") (pin "1") (pinfunction "1_1") (pintype "passive"))
      (node (ref "U1") (pin "5") (pinfunction "BOUT2_5") (pintype "output"))
    )
    (net (code "55") (name "/NR") (class "Default")
      (node (ref "C9") (pin "2") (pinfunction "2_2") (pintype "passive"))
      (node (ref "U15") (pin "4") (pinfunction "NR_4") (pintype "passive"))
    )
    (net (code "56") (name "/PWM0") (class "Default")
      (node (ref "J1") (pin "4") (pinfunction "4_4") (pintype "passive"))
      (node (ref "RN3") (pin "9") (pinfunction "16_9") (pintype "passive"))
    )
    (net (code "57") (name "/PWM1") (class "Default")
      (node (ref "J1") (pin "3") (pinfunction "3_3") (pintype "passive"))
      (node (ref "RN3") (pin "10") (pinfunction "15_10") (pintype "passive"))
    )
    (net (code "58") (name "/PWM2") (class "Default")
      (node (ref "J1") (pin "2") (pinfunction "2_2") (pintype "passive"))
      (node (ref "RN3") (pin "11") (pinfunction "14_11") (pintype "passive"))
    )
    (net (code "59") (name "/PWM3") (class "Default")
      (node (ref "J1") (pin "1") (pinfunction "1_1") (pintype "passive"))
      (node (ref "RN3") (pin "12") (pinfunction "13_12") (pintype "passive"))
    )
    (net (code "60") (name "/PWM4") (class "Default")
      (node (ref "J7") (pin "4") (pinfunction "4_4") (pintype "passive"))
      (node (ref "RN3") (pin "13") (pinfunction "12_13") (pintype "passive"))
    )
    (net (code "61") (name "/PWM5") (class "Default")
      (node (ref "J7") (pin "3") (pinfunction "3_3") (pintype "passive"))
      (node (ref "RN3") (pin "14") (pinfunction "11_14") (pintype "passive"))
    )
    (net (code "62") (name "/PWM6") (class "Default")
      (node (ref "J7") (pin "2") (pinfunction "2_2") (pintype "passive"))
      (node (ref "RN3") (pin "15") (pinfunction "10_15") (pintype "passive"))
    )
    (net (code "63") (name "/PWM7") (class "Default")
      (node (ref "J7") (pin "1") (pinfunction "1_1") (pintype "passive"))
      (node (ref "RN3") (pin "16") (pinfunction "9_16") (pintype "passive"))
    )
    (net (code "68") (name "/PWM12") (class "Default")
      (node (ref "RN4") (pin "9") (pinfunction "16_9") (pintype "passive"))
      (node (ref "U1") (pin "16") (pinfunction "AIN1_16") (pintype "input"))
    )
    (net (code "69") (name "/PWM13") (class "Default")
      (node (ref "RN4") (pin "10") (pinfunction "15_10") (pintype "passive"))
      (node (ref "U1") (pin "15") (pinfunction "AIN2_15") (pintype "input"))
    )
    (net (code "70") (name "/PWM14") (class "Default")
      (node (ref "RN4") (pin "11") (pinfunction "14_11") (pintype "passive"))
      (node (ref "U1") (pin "10") (pinfunction "BIN2_10") (pintype "input"))
    )
    (net (code "71") (name "/PWM15") (class "Default")
      (node (ref "RN4") (pin "12") (pinfunction "13_12") (pintype "passive"))
      (node (ref "U1") (pin "9") (pinfunction "BIN1_9") (pintype "input"))
    )
    (net (code "72") (name "/PWM_A0") (class "Default")
      (node (ref "PD6") (pin "1") (pinfunction "1_1") (pintype "passive"))
      (node (ref "R11") (pin "2") (pinfunction "2_2") (pintype "passive"))
      (node (ref "U12") (pin "26") (pinfunction "A0_26") (pintype "input"))
    )
    (net (code "73") (name "/PWM_A1") (class "Default")
      (node (ref "PD5") (pin "1") (pinfunction "1_1") (pintype "passive"))
      (node (ref "R10") (pin "2") (pinfunction "2_2") (pintype "passive"))
      (node (ref "U12") (pin "27") (pinfunction "A1_27") (pintype "input"))
    )
    (net (code "74") (name "/PWM_A2") (class "Default")
      (node (ref "PD4") (pin "1") (pinfunction "1_1") (pintype "passive"))
      (node (ref "R9") (pin "2") (pinfunction "2_2") (pintype "passive"))
      (node (ref "U12") (pin "28") (pinfunction "A2_28") (pintype "input"))
    )
    (net (code "75") (name "/PWM_A3") (class "Default")
      (node (ref "PD3") (pin "1") (pinfunction "1_1") (pintype "passive"))
      (node (ref "R7") (pin "2") (pinfunction "2_2") (pintype "passive"))
      (node (ref "U12") (pin "1") (pinfunction "A3_1") (pintype "input"))
    )
    (net (code "76") (name "/PWM_A4") (class "Default")
      (node (ref "PD2") (pin "1") (pinfunction "1_1") (pintype "passive"))
      (node (ref "R6") (pin "2") (pinfunction "2_2") (pintype "passive"))
      (node (ref "U12") (pin "2") (pinfunction "A4_2") (pintype "input"))
    )
    (net (code "77") (name "/PWM_A5") (class "Default")
      (node (ref "PD1") (pin "1") (pinfunction "1_1") (pintype "passive"))
      (node (ref "R5") (pin "2") (pinfunction "2_2") (pintype "passive"))
      (node (ref "U12") (pin "21") (pinfunction "A5_21") (pintype "input"))
    )
    (net (code "78") (name "/PWM_OE") (class "Default")
      (node (ref "R12") (pin "2") (pinfunction "2_2") (pintype "passive"))
      (node (ref "U12") (pin "20") (pinfunction "~{OE}_20") (pintype "input"))
    )
    (net (code "79") (name "/SW") (class "Default")
      (node (ref "D1") (pin "1") (pinfunction "C_1") (pintype "passive"))
      (node (ref "L1") (pin "1") (pinfunction "1_1") (pintype "passive"))
      (node (ref "U3") (pin "2") (pinfunction "OUT_2") (pintype "power_in"))
    )
    (net (code "80") (name "3.3V") (class "Default")
      (node (ref "J2") (pin "1") (pinfunction "1_1") (pintype "passive"))
      (node (ref "J2") (pin "17") (pinfunction "17_17") (pintype "passive"))
      (node (ref "S2") (pin "1") (pinfunction "NC_1") (pintype "passive"))
    )
    (net (code "81") (name "5V") (class "Default")
      (node (ref "C11") (pin "1") (pinfunction "1_1") (pintype "passive"))
      (node (ref "C15") (pin "1") (pinfunction "1_1") (pintype "passive"))
      (node (ref "C22") (pin "1") (pinfunction "1_1") (pintype "passive"))
      (node (ref "C4") (pin "2") (pinfunction "2_2") (pintype "passive"))
      (node (ref "C8") (pin "2") (pinfunction "A_2") (pintype "passive"))
      (node (ref "J1") (pin "5") (pinfunction "5_5") (pintype "passive"))
      (node (ref "J1") (pin "6") (pinfunction "6_6") (pintype "passive"))
      (node (ref "J1") (pin "7") (pinfunction "7_7") (pintype "passive"))
      (node (ref "J1") (pin "8") (pinfunction "8_8") (pintype "passive"))
      (node (ref "J2") (pin "2") (pinfunction "2_2") (pintype "passive"))
      (node (ref "J2") (pin "4") (pinfunction "4_4") (pintype "passive"))
      (node (ref "J3") (pin "1") (pinfunction "1_1") (pintype "passive"))
      (node (ref "J4") (pin "1") (pinfunction "1_1") (pintype "passive"))
      (node (ref "J5") (pin "1") (pinfunction "1_1") (pintype "passive"))
      (node (ref "J6") (pin "1") (pinfunction "1_1") (pintype "passive"))
      (node (ref "J7") (pin "5") (pinfunction "5_5") (pintype "passive"))
      (node (ref "J7") (pin "6") (pinfunction "6_6") (pintype "passive"))
      (node (ref "J7") (pin "7") (pinfunction "7_7") (pintype "passive"))
      (node (ref "J7") (pin "8") (pinfunction "8_8") (pintype "passive"))
      (node (ref "J8") (pin "1") (pinfunction "1_1") (pintype "passive"))
      (node (ref "L1") (pin "2") (pinfunction "2_2") (pintype "passive"))
      (node (ref "PD1") (pin "2") (pinfunction "0_2") (pintype "passive"))
      (node (ref "PD2") (pin "2") (pinfunction "0_2") (pintype "passive"))
      (node (ref "PD3") (pin "2") (pinfunction "0_2") (pintype "passive"))
      (node (ref "PD4") (pin "2") (pinfunction "0_2") (pintype "passive"))
      (node (ref "PD5") (pin "2") (pinfunction "0_2") (pintype "passive"))
      (node (ref "PD6") (pin "2") (pinfunction "0_2") (pintype "passive"))
      (node (ref "R13") (pin "1") (pinfunction "1_1") (pintype "passive"))
      (node (ref "R2") (pin "1") (pinfunction "1_1") (pintype "passive"))
      (node (ref "R8") (pin "1") (pinfunction "1_1") (pintype "passive"))
      (node (ref "U1") (pin "1") (pinfunction "VREF_1") (pintype "power_in"))
      (node (ref "U12") (pin "25") (pinfunction "VDD_25") (pintype "power_in"))
      (node (ref "U15") (pin "1") (pinfunction "IN_1") (pintype "power_in"))
      (node (ref "U15") (pin "3") (pinfunction "EN_3") (pintype "input"))
      (node (ref "U18") (pin "15") (pinfunction "VREF_15") (pintype "input"))
      (node (ref "U18") (pin "16") (pinfunction "VDD_16") (pintype "power_in"))
      (node (ref "U9") (pin "10") (pinfunction "VS_10") (pintype "passive"))
      (node (ref "U9") (pin "5") (pinfunction "A0_5") (pintype "input"))
      (node (ref "VR1") (pin "1") (pinfunction "CCW_1") (pintype "passive"))
    )
    (net (code "82") (name "BM+") (class "Default")
      (node (ref "C1") (pin "1") (pinfunction "1_1") (pintype "passive"))
      (node (ref "C16") (pin "1") (pinfunction "1_1") (pintype "passive"))
      (node (ref "C17") (pin "1") (pinfunction "1_1") (pintype "passive"))
      (node (ref "C2") (pin "1") (pinfunction "1_1") (pintype "passive"))
      (node (ref "LED5") (pin "2") (pinfunction "A_2") (pintype "passive"))
      (node (ref "LED6") (pin "2") (pinfunction "A_2") (pintype "passive"))
      (node (ref "LED7") (pin "2") (pinfunction "A_2") (pintype "passive"))
      (node (ref "LED8") (pin "2") (pinfunction "A_2") (pintype "passive"))
      (node (ref "R26") (pin "2") (pinfunction "2_2") (pintype "passive"))
      (node (ref "R27") (pin "1") (pinfunction "1_1") (pintype "passive"))
      (node (ref "U1") (pin "12") (pinfunction "VM_12") (pintype "power_in"))
      (node (ref "U2") (pin "2") (pinfunction "VCC+_2") (pintype "power_in"))
      (node (ref "U3") (pin "1") (pinfunction "VIN_1") (pintype "power_in"))
      (node (ref "U9") (pin "14") (pinfunction "IN-_14") (pintype "passive"))
      (node (ref "U9") (pin "15") (pinfunction "IN-_15") (pintype "passive"))
      (node (ref "U9") (pin "16") (pinfunction "IN-_16") (pintype "passive"))
    )
    (net (code "83") (name "GND") (class "Default")
      (node (ref "C1") (pin "2") (pinfunction "2_2") (pintype "passive"))
      (node (ref "C10") (pin "2") (pinfunction "2_2") (pintype "passive"))
      (node (ref "C11") (pin "2") (pinfunction "2_2") (pintype "passive"))
      (node (ref "C12") (pin "2") (pinfunction "2_2") (pintype "passive"))
      (node (ref "C13") (pin "2") (pinfunction "2_2") (pintype "passive"))
      (node (ref "C14") (pin "1") (pinfunction "1_1") (pintype "passive"))
      (node (ref "C15") (pin "2") (pinfunction "2_2") (pintype "passive"))
      (node (ref "C16") (pin "2") (pinfunction "2_2") (pintype "passive"))
      (node (ref "C17") (pin "2") (pinfunction "2_2") (pintype "passive"))
      (node (ref "C2") (pin "2") (pinfunction "2_2") (pintype "passive"))
      (node (ref "C22") (pin "2") (pinfunction "2_2") (pintype "passive"))
      (node (ref "C3") (pin "1") (pinfunction "1_1") (pintype "passive"))
      (node (ref "C4") (pin "1") (pinfunction "1_1") (pintype "passive"))
      (node (ref "C8") (pin "1") (pinfunction "C_1") (pintype "passive"))
      (node (ref "C9") (pin "1") (pinfunction "1_1") (pintype "passive"))
      (node (ref "D1") (pin "2") (pinfunction "A_2") (pintype "passive"))
      (node (ref "J1") (pin "10") (pinfunction "10_10") (pintype "passive"))
      (node (ref "J1") (pin "11") (pinfunction "11_11") (pintype "passive"))
      (node (ref "J1") (pin "12") (pinfunction "12_12") (pintype "passive"))
      (node (ref "J1") (pin "9") (pinfunction "9_9") (pintype "passive"))
      (node (ref "J10") (pin "3") (pinfunction "MNT_1_3") (pintype "passive"))
      (node (ref "J10") (pin "4") (pinfunction "MNT_2_4") (pintype "passive"))
      (node (ref "J11") (pin "2") (pinfunction "2_2") (pintype "passive"))
      (node (ref "J11") (pin "3") (pinfunction "MNT_1_3") (pintype "passive"))
      (node (ref "J11") (pin "4") (pinfunction "MNT_2_4") (pintype "passive"))
      (node (ref "J2") (pin "14") (pinfunction "14_14") (pintype "passive"))
      (node (ref "J2") (pin "20") (pinfunction "20_20") (pintype "passive"))
      (node (ref "J2") (pin "25") (pinfunction "25_25") (pintype "passive"))
      (node (ref "J2") (pin "30") (pinfunction "30_30") (pintype "passive"))
      (node (ref "J2") (pin "34") (pinfunction "34_34") (pintype "passive"))
      (node (ref "J2") (pin "39") (pinfunction "39_39") (pintype "passive"))
      (node (ref "J2") (pin "6") (pinfunction "6_6") (pintype "passive"))
      (node (ref "J2") (pin "9") (pinfunction "9_9") (pintype "passive"))
      (node (ref "J3") (pin "4") (pinfunction "4_4") (pintype "passive"))
      (node (ref "J3") (pin "5") (pinfunction "MNT_1_5") (pintype "passive"))
      (node (ref "J3") (pin "6") (pinfunction "MNT_2_6") (pintype "passive"))
      (node (ref "J4") (pin "4") (pinfunction "4_4") (pintype "passive"))
      (node (ref "J4") (pin "5") (pinfunction "MNT_1_5") (pintype "passive"))
      (node (ref "J4") (pin "6") (pinfunction "MNT_2_6") (pintype "passive"))
      (node (ref "J5") (pin "3") (pinfunction "3_3") (pintype "passive"))
      (node (ref "J5") (pin "4") (pinfunction "MNT_1_4") (pintype "passive"))
      (node (ref "J5") (pin "5") (pinfunction "MNT_2_5") (pintype "passive"))
      (node (ref "J6") (pin "4") (pinfunction "4_4") (pintype "passive"))
      (node (ref "J6") (pin "5") (pinfunction "MNT_1_5") (pintype "passive"))
      (node (ref "J6") (pin "6") (pinfunction "MNT_2_6") (pintype "passive"))
      (node (ref "J7") (pin "10") (pinfunction "10_10") (pintype "passive"))
      (node (ref "J7") (pin "11") (pinfunction "11_11") (pintype "passive"))
      (node (ref "J7") (pin "12") (pinfunction "12_12") (pintype "passive"))
      (node (ref "J7") (pin "9") (pinfunction "9_9") (pintype "passive"))
      (node (ref "J8") (pin "4") (pinfunction "4_4") (pintype "passive"))
      (node (ref "J8") (pin "5") (pinfunction "MNT_1_5") (pintype "passive"))
      (node (ref "J8") (pin "6") (pinfunction "MNT_2_6") (pintype "passive"))
      (node (ref "J9") (pin "3") (pinfunction "MNT_1_3") (pintype "passive"))
      (node (ref "J9") (pin "4") (pinfunction "MNT_2_4") (pintype "passive"))
      (node (ref "LED1") (pin "1") (pinfunction "C_1") (pintype "passive"))
      (node (ref "PTH1") (pin "0") (pinfunction "0_0") (pintype "passive"))
      (node (ref "PTH2") (pin "0") (pinfunction "0_0") (pintype "passive"))
      (node (ref "PTH3") (pin "0") (pinfunction "0_0") (pintype "passive"))
      (node (ref "PTH4") (pin "0") (pinfunction "0_0") (pintype "passive"))
      (node (ref "R1") (pin "2") (pinfunction "2_2") (pintype "passive"))
      (node (ref "R10") (pin "1") (pinfunction "1_1") (pintype "passive"))
      (node (ref "R11") (pin "1") (pinfunction "1_1") (pintype "passive"))
      (node (ref "R12") (pin "1") (pinfunction "1_1") (pintype "passive"))
      (node (ref "R24") (pin "2") (pinfunction "2_2") (pintype "passive"))
      (node (ref "R3") (pin "1") (pinfunction "1_1") (pintype "passive"))
      (node (ref "R35") (pin "2") (pinfunction "2_2") (pintype "passive"))
      (node (ref "R36") (pin "1") (pinfunction "1_1") (pintype "passive"))
      (node (ref "R37") (pin "1") (pinfunction "1_1") (pintype "passive"))
      (node (ref "R4") (pin "1") (pinfunction "1_1") (pintype "passive"))
      (node (ref "R5") (pin "1") (pinfunction "1_1") (pintype "passive"))
      (node (ref "R6") (pin "1") (pinfunction "1_1") (pintype "passive"))
      (node (ref "R7") (pin "1") (pinfunction "1_1") (pintype "passive"))
      (node (ref "R9") (pin "1") (pinfunction "1_1") (pintype "passive"))
      (node (ref "S2") (pin "3") (pinfunction "NO_3") (pintype "passive"))
      (node (ref "U1") (pin "13") (pinfunction "GND_13") (pintype "power_in"))
      (node (ref "U1") (pin "17") (pinfunction "EXP_17") (pintype "passive"))
      (node (ref "U1") (pin "3") (pinfunction "PGNDA_3") (pintype "power_in"))
      (node (ref "U1") (pin "6") (pinfunction "PGNDB_6") (pintype "power_in"))
      (node (ref "U12") (pin "11") (pinfunction "VSS_11") (pintype "power_in"))
      (node (ref "U12") (pin "29") (pinfunction "EXP_29") (pintype "power_in"))
      (node (ref "U14") (pin "11") (pinfunction "FSYNC_11") (pintype "passive"))
      (node (ref "U14") (pin "18") (pinfunction "GND_18") (pintype "passive"))
      (node (ref "U14") (pin "20") (pinfunction "RESV_2_20") (pintype "passive"))
      (node (ref "U14") (pin "25") (pinfunction "EP_25") (pintype "passive"))
      (node (ref "U14") (pin "9") (pinfunction "SDO/ADO_9") (pintype "passive"))
      (node (ref "U15") (pin "2") (pinfunction "GND_2") (pintype "power_in"))
      (node (ref "U18") (pin "14") (pinfunction "AGND_14") (pintype "power_in"))
      (node (ref "U18") (pin "9") (pinfunction "DGND_9") (pintype "power_in"))
      (node (ref "U2") (pin "11") (pinfunction "VCC-_11") (pintype "power_in"))
      (node (ref "U2") (pin "17") (pinfunction "NC_17") (pintype "passive"))
      (node (ref "U3") (pin "3") (pinfunction "GND_3") (pintype "power_in"))
      (node (ref "U3") (pin "5") (pinfunction "~{ON}/OFF_5") (pintype "input"))
      (node (ref "U3") (pin "6") (pinfunction "TAB_6") (pintype "power_in"))
      (node (ref "U8") (pin "3") (pinfunction "A_3") (pintype "passive"))
      (node (ref "U9") (pin "11") (pinfunction "GND_11") (pintype "power_in"))
      (node (ref "U9") (pin "4") (pinfunction "A1_4") (pintype "input"))
      (node (ref "U9") (pin "6") (pinfunction "GND_6") (pintype "power_in"))
    )
    (net (code "84") (name "Net-(LED1-A)") (class "Default")
      (node (ref "LED1") (pin "2") (pinfunction "A_2") (pintype "passive"))
      (node (ref "R8") (pin "2") (pinfunction "2_2") (pintype "passive"))
    )
    (net (code "85") (name "Net-(LED5-C)") (class "Default")
      (node (ref "LED5") (pin "1") (pinfunction "C_1") (pintype "passive"))
      (node (ref "RN1") (pin "6") (pinfunction "6_6") (pintype "passive"))
    )
    (net (code "86") (name "Net-(LED6-C)") (class "Default")
      (node (ref "LED6") (pin "1") (pinfunction "C_1") (pintype "passive"))
      (node (ref "RN1") (pin "7") (pinfunction "7_7") (pintype "passive"))
    )
    (net (code "87") (name "Net-(LED7-C)") (class "Default")
      (node (ref "LED7") (pin "1") (pinfunction "C_1") (pintype "passive"))
      (node (ref "RN1") (pin "8") (pinfunction "8_8") (pintype "passive"))
    )
    (net (code "88") (name "Net-(LED8-C)") (class "Default")
      (node (ref "LED8") (pin "1") (pinfunction "C_1") (pintype "passive"))
      (node (ref "RN1") (pin "5") (pinfunction "5_5") (pintype "passive"))
    )
    (net (code "89") (name "Net-(RN3-1)") (class "Default")
      (node (ref "RN3") (pin "8") (pinfunction "1_8") (pintype "passive"))
      (node (ref "U12") (pin "3") (pinfunction "LED0_3") (pintype "output"))
    )
    (net (code "90") (name "Net-(RN3-2)") (class "Default")
      (node (ref "RN3") (pin "7") (pinfunction "2_7") (pintype "passive"))
      (node (ref "U12") (pin "4") (pinfunction "LED1_4") (pintype "output"))
    )
    (net (code "91") (name "Net-(RN3-3)") (class "Default")
      (node (ref "RN3") (pin "6") (pinfunction "3_6") (pintype "passive"))
      (node (ref "U12") (pin "5") (pinfunction "LED2_5") (pintype "output"))
    )
    (net (code "92") (name "Net-(RN3-4)") (class "Default")
      (node (ref "RN3") (pin "5") (pinfunction "4_5") (pintype "passive"))
      (node (ref "U12") (pin "6") (pinfunction "LED3_6") (pintype "output"))
    )
    (net (code "93") (name "Net-(RN3-5)") (class "Default")
      (node (ref "RN3") (pin "4") (pinfunction "5_4") (pintype "passive"))
      (node (ref "U12") (pin "7") (pinfunction "LED4_7") (pintype "output"))
    )
    (net (code "94") (name "Net-(RN3-6)") (class "Default")
      (node (ref "RN3") (pin "3") (pinfunction "6_3") (pintype "passive"))
      (node (ref "U12") (pin "8") (pinfunction "LED5_8") (pintype "output"))
    )
    (net (code "95") (name "Net-(RN3-7)") (class "Default")
      (node (ref "RN3") (pin "2") (pinfunction "7_2") (pintype "passive"))
      (node (ref "U12") (pin "9") (pinfunction "LED6_9") (pintype "output"))
    )
    (net (code "96") (name "Net-(RN3-8)") (class "Default")
      (node (ref "RN3") (pin "1") (pinfunction "8_1") (pintype "passive"))
      (node (ref "U12") (pin "10") (pinfunction "LED7_10") (pintype "output"))
    )
    (net (code "97") (name "Net-(RN4-1)") (class "Default")
      (node (ref "RN4") (pin "8") (pinfunction "1_8") (pintype "passive"))
      (node (ref "U12") (pin "16") (pinfunction "LED12_16") (pintype "output"))
    )
    (net (code "98") (name "Net-(RN4-2)") (class "Default")
      (node (ref "RN4") (pin "7") (pinfunction "2_7") (pintype "passive"))
      (node (ref "U12") (pin "17") (pinfunction "LED13_17") (pintype "output"))
    )
    (net (code "99") (name "Net-(RN4-3)") (class "Default")
      (node (ref "RN4") (pin "6") (pinfunction "3_6") (pintype "passive"))
      (node (ref "U12") (pin "18") (pinfunction "LED14_18") (pintype "output"))
    )
    (net (code "100") (name "Net-(RN4-4)") (class "Default")
      (node (ref "RN4") (pin "5") (pinfunction "4_5") (pintype "passive"))
      (node (ref "U12") (pin "19") (pinfunction "LED15_19") (pintype "output"))
    )
    (net (code "101") (name "Net-(S2-COM)") (class "Default")
      (node (ref "R14") (pin "1") (pinfunction "1_1") (pintype "passive"))
      (node (ref "S2") (pin "2") (pinfunction "COM_2") (pintype "passive"))
    )
    (net (code "102") (name "Net-(U8-C)") (class "Default")
      (node (ref "R27") (pin "2") (pinfunction "2_2") (pintype "passive"))
      (node (ref "R28") (pin "1") (pinfunction "1_1") (pintype "passive"))
      (node (ref "U8") (pin "1") (pinfunction "C_1") (pintype "passive"))
      (node (ref "U8") (pin "2") (pinfunction "REF_2") (pintype "passive"))
    )
    (net (code "103") (name "Net-(U14-REGOUT)") (class "Default")
      (node (ref "C13") (pin "1") (pinfunction "1_1") (pintype "passive"))
      (node (ref "U14") (pin "10") (pinfunction "REGOUT_10") (pintype "passive"))
    )
    (net (code "104") (name "unconnected-(RN4-5-Pad4)") (class "Default")
      (node (ref "RN4") (pin "4") (pinfunction "5_4") (pintype "passive+no_connect"))
    )
    (net (code "105") (name "unconnected-(RN4-6-Pad3)") (class "Default")
      (node (ref "RN4") (pin "3") (pinfunction "6_3") (pintype "passive+no_connect"))
    )
    (net (code "106") (name "unconnected-(RN4-7-Pad2)") (class "Default")
      (node (ref "RN4") (pin "2") (pinfunction "7_2") (pintype "passive+no_connect"))
    )
    (net (code "107") (name "unconnected-(RN4-8-Pad1)") (class "Default")
      (node (ref "RN4") (pin "1") (pinfunction "8_1") (pintype "passive+no_connect"))
    )
    (net (code "108") (name "unconnected-(RN4-9-Pad16)") (class "Default")
      (node (ref "RN4") (pin "16") (pinfunction "9_16") (pintype "passive+no_connect"))
    )
    (net (code "109") (name "unconnected-(RN4-10-Pad15)") (class "Default")
      (node (ref "RN4") (pin "15") (pinfunction "10_15") (pintype "passive+no_connect"))
    )
    (net (code "110") (name "unconnected-(RN4-11-Pad14)") (class "Default")
      (node (ref "RN4") (pin "14") (pinfunction "11_14") (pintype "passive+no_connect"))
    )
    (net (code "111") (name "unconnected-(RN4-12-Pad13)") (class "Default")
      (node (ref "RN4") (pin "13") (pinfunction "12_13") (pintype "passive+no_connect"))
    )
    (net (code "112") (name "unconnected-(S1-Pad1)") (class "Default")
      (node (ref "S1") (pin "1") (pinfunction "1_1") (pintype "passive+no_connect"))
    )
    (net (code "113") (name "unconnected-(U2-NC-Pad3)") (class "Default")
      (node (ref "U2") (pin "3") (pinfunction "NC_3") (pintype "passive+no_connect"))
    )
    (net (code "114") (name "unconnected-(U2-NC-Pad10)") (class "Default")
      (node (ref "U2") (pin "10") (pinfunction "NC_10") (pintype "passive+no_connect"))
    )
    (net (code "115") (name "unconnected-(U9-NC-Pad13)") (class "Default")
      (node (ref "U9") (pin "13") (pinfunction "NC_13") (pintype "passive+no_connect"))
    )
    (net (code "116") (name "unconnected-(U12-EXTCLK-Pad22)") (class "Default")
      (node (ref "U12") (pin "22") (pinfunction "EXTCLK_22") (pintype "input+no_connect"))
    )
    (net (code "117") (name "unconnected-(U12-LED8-Pad12)") (class "Default")
      (node (ref "U12") (pin "12") (pinfunction "LED8_12") (pintype "output+no_connect"))
    )
    (net (code "118") (name "unconnected-(U12-LED9-Pad13)") (class "Default")
      (node (ref "U12") (pin "13") (pinfunction "LED9_13") (pintype "output+no_connect"))
    )
    (net (code "119") (name "unconnected-(U12-LED10-Pad14)") (class "Default")
      (node (ref "U12") (pin "14") (pinfunction "LED10_14") (pintype "output+no_connect"))
    )
    (net (code "120") (name "unconnected-(U12-LED11-Pad15)") (class "Default")
      (node (ref "U12") (pin "15") (pinfunction "LED11_15") (pintype "output+no_connect"))
    )
    (net (code "121") (name "unconnected-(U14-AUX_CL-Pad7)") (class "Default")
      (node (ref "U14") (pin "7") (pinfunction "AUX_CL_7") (pintype "passive+no_connect"))
    )
    (net (code "122") (name "unconnected-(U14-AUX_DA-Pad21)") (class "Default")
      (node (ref "U14") (pin "21") (pinfunction "AUX_DA_21") (pintype "passive+no_connect"))
    )
    (net (code "123") (name "unconnected-(U14-INT1-Pad12)") (class "Default")
      (node (ref "U14") (pin "12") (pinfunction "INT1_12") (pintype "passive+no_connect"))
    )
    (net (code "124") (name "unconnected-(U14-NC_1-Pad1)") (class "Default")
      (node (ref "U14") (pin "1") (pinfunction "NC_1_1") (pintype "passive+no_connect"))
    )
    (net (code "125") (name "unconnected-(U14-NC_2-Pad2)") (class "Default")
      (node (ref "U14") (pin "2") (pinfunction "NC_2_2") (pintype "passive+no_connect"))
    )
    (net (code "126") (name "unconnected-(U14-NC_3-Pad3)") (class "Default")
      (node (ref "U14") (pin "3") (pinfunction "NC_3_3") (pintype "passive+no_connect"))
    )
    (net (code "127") (name "unconnected-(U14-NC_4-Pad4)") (class "Default")
      (node (ref "U14") (pin "4") (pinfunction "NC_4_4") (pintype "passive+no_connect"))
    )
    (net (code "128") (name "unconnected-(U14-NC_5-Pad5)") (class "Default")
      (node (ref "U14") (pin "5") (pinfunction "NC_5_5") (pintype "passive+no_connect"))
    )
    (net (code "129") (name "unconnected-(U14-NC_6-Pad6)") (class "Default")
      (node (ref "U14") (pin "6") (pinfunction "NC_6_6") (pintype "passive+no_connect"))
    )
    (net (code "130") (name "unconnected-(U14-NC_7-Pad14)") (class "Default")
      (node (ref "U14") (pin "14") (pinfunction "NC_7_14") (pintype "passive+no_connect"))
    )
    (net (code "131") (name "unconnected-(U14-NC_8-Pad15)") (class "Default")
      (node (ref "U14") (pin "15") (pinfunction "NC_8_15") (pintype "passive+no_connect"))
    )
    (net (code "132") (name "unconnected-(U14-NC_9-Pad16)") (class "Default")
      (node (ref "U14") (pin "16") (pinfunction "NC_9_16") (pintype "passive+no_connect"))
    )
    (net (code "133") (name "unconnected-(U14-NC_10-Pad17)") (class "Default")
      (node (ref "U14") (pin "17") (pinfunction "NC_10_17") (pintype "passive+no_connect"))
    )
    (net (code "134") (name "unconnected-(U14-RESV_1-Pad19)") (class "Default")
      (node (ref "U14") (pin "19") (pinfunction "RESV_1_19") (pintype "passive+no_connect"))
    )
    (net (code "135") (name "unconnected-(VR1-CW-Pad3)") (class "Default")
      (node (ref "VR1") (pin "3") (pinfunction "CW_3") (pintype "passive+no_connect"))
    )
  )
)
